# EFM32_power.net
KiCad netlist of a schematic drawn in Altium Designer
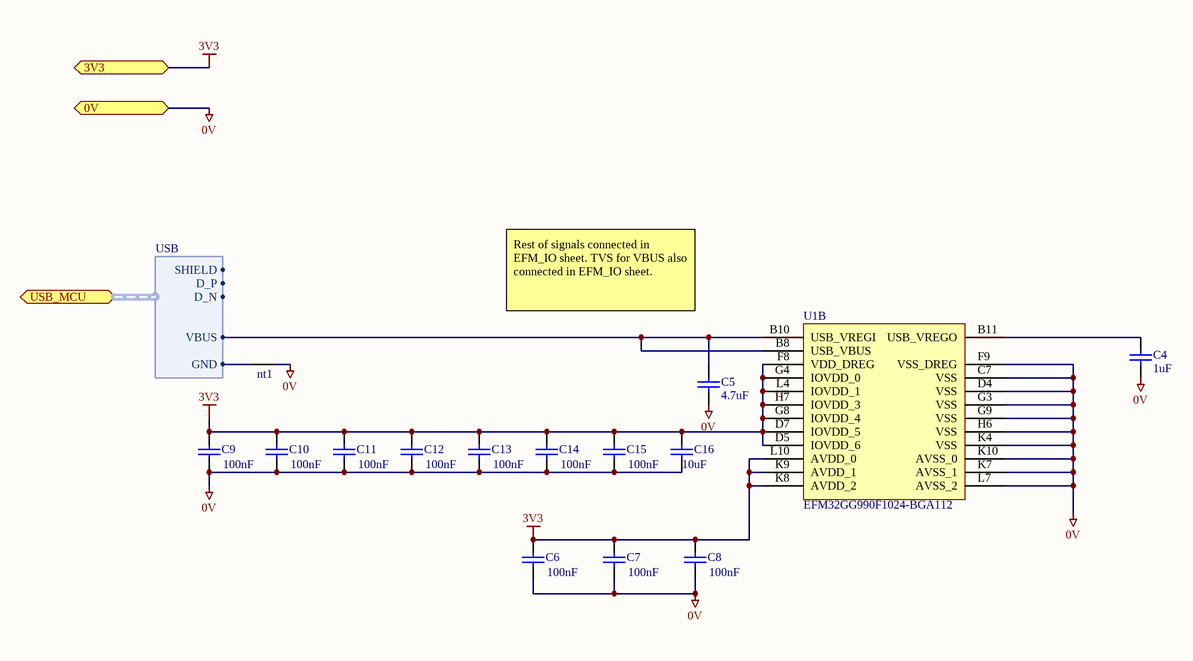
[diagram p0: EFM32_power.SchDoc]

(export (version "E")
  (design (tool "Eeschema 10.0.6"))
  (components
    (comp (ref "C4")
      (value "1uF")
      (footprint "CAPC0603(1608)100_M")
      (description "CAP 1uF 16V ±5% 0603 (1608 Metric) Thickness 1mm SMD")
      (fields (field (name "TOLERANCE") "Â±5%") (field (name "Comment") "CAP 1uF 16V 0603(1608)"))
      (libsource (lib "Altium Content Vault") (part "CMP-1035-02736-1"))
    )
    (comp (ref "C5")
      (value "4.7uF")
      (footprint "CAPC0603(1608)100_M")
      (description "CAP 4.7uF 16V ±10% 0603 (1608 Metric) Thickness 1mm SMD")
      (fields (field (name "TOLERANCE") "Â±10%") (field (name "Comment") "CAP 4.7uF 16V 0603(1608)"))
      (libsource (lib "Altium Content Vault") (part "CMP-1035-02788-1"))
    )
    (comp (ref "C6")
      (value "100nF")
      (footprint "CAPC0603(1608)100_M")
      (description "CAP 100nF 16V ±5% 0603 (1608 Metric) Thickness 1mm SMD")
      (fields (field (name "TOLERANCE") "Â±5%") (field (name "Comment") "CAP 100nF 16V 0603(1608)"))
      (libsource (lib "Altium Content Vault") (part "CMP-1035-02583-1"))
    )
    (comp (ref "C7")
      (value "100nF")
      (footprint "CAPC0603(1608)100_M")
      (description "CAP 100nF 16V ±5% 0603 (1608 Metric) Thickness 1mm SMD")
      (fields (field (name "TOLERANCE") "Â±5%") (field (name "Comment") "CAP 100nF 16V 0603(1608)"))
      (libsource (lib "Altium Content Vault") (part "CMP-1035-02583-1"))
    )
    (comp (ref "C8")
      (value "100nF")
      (footprint "CAPC0603(1608)100_M")
      (description "CAP 100nF 16V ±5% 0603 (1608 Metric) Thickness 1mm SMD")
      (fields (field (name "TOLERANCE") "Â±5%") (field (name "Comment") "CAP 100nF 16V 0603(1608)"))
      (libsource (lib "Altium Content Vault") (part "CMP-1035-02583-1"))
    )
    (comp (ref "C9")
      (value "100nF")
      (footprint "CAPC0603(1608)100_M")
      (description "CAP 100nF 16V ±5% 0603 (1608 Metric) Thickness 1mm SMD")
      (fields (field (name "TOLERANCE") "Â±5%") (field (name "Comment") "CAP 100nF 16V 0603(1608)"))
      (libsource (lib "Altium Content Vault") (part "CMP-1035-02583-1"))
    )
    (comp (ref "C10")
      (value "100nF")
      (footprint "CAPC0603(1608)100_M")
      (description "CAP 100nF 16V ±5% 0603 (1608 Metric) Thickness 1mm SMD")
      (fields (field (name "TOLERANCE") "Â±5%") (field (name "Comment") "CAP 100nF 16V 0603(1608)"))
      (libsource (lib "Altium Content Vault") (part "CMP-1035-02583-1"))
    )
    (comp (ref "C11")
      (value "100nF")
      (footprint "CAPC0603(1608)100_M")
      (description "CAP 100nF 16V ±5% 0603 (1608 Metric) Thickness 1mm SMD")
      (fields (field (name "TOLERANCE") "Â±5%") (field (name "Comment") "CAP 100nF 16V 0603(1608)"))
      (libsource (lib "Altium Content Vault") (part "CMP-1035-02583-1"))
    )
    (comp (ref "C12")
      (value "100nF")
      (footprint "CAPC0603(1608)100_M")
      (description "CAP 100nF 16V ±5% 0603 (1608 Metric) Thickness 1mm SMD")
      (fields (field (name "TOLERANCE") "Â±5%") (field (name "Comment") "CAP 100nF 16V 0603(1608)"))
      (libsource (lib "Altium Content Vault") (part "CMP-1035-02583-1"))
    )
    (comp (ref "C13")
      (value "100nF")
      (footprint "CAPC0603(1608)100_M")
      (description "CAP 100nF 16V ±5% 0603 (1608 Metric) Thickness 1mm SMD")
      (fields (field (name "TOLERANCE") "Â±5%") (field (name "Comment") "CAP 100nF 16V 0603(1608)"))
      (libsource (lib "Altium Content Vault") (part "CMP-1035-02583-1"))
    )
    (comp (ref "C14")
      (value "100nF")
      (footprint "CAPC0603(1608)100_M")
      (description "CAP 100nF 16V ±5% 0603 (1608 Metric) Thickness 1mm SMD")
      (fields (field (name "TOLERANCE") "Â±5%") (field (name "Comment") "CAP 100nF 16V 0603(1608)"))
      (libsource (lib "Altium Content Vault") (part "CMP-1035-02583-1"))
    )
    (comp (ref "C15")
      (value "100nF")
      (footprint "CAPC0603(1608)100_M")
      (description "CAP 100nF 16V ±5% 0603 (1608 Metric) Thickness 1mm SMD")
      (fields (field (name "TOLERANCE") "Â±5%") (field (name "Comment") "CAP 100nF 16V 0603(1608)"))
      (libsource (lib "Altium Content Vault") (part "CMP-1035-02583-1"))
    )
    (comp (ref "C16")
      (value "10uF")
      (footprint "CAPC0603(1608)100_M")
      (description "CAP 10uF 10V ±10% 0603 (1608 Metric) Thickness 1mm SMD")
      (fields (field (name "TOLERANCE") "Â±10%") (field (name "Comment") "CAP 10uF 10V 0603(1608)"))
      (libsource (lib "Altium Content Vault") (part "CMP-1035-02799-1"))
    )
    (comp (ref "nt1")
      (value "net tie")
      (footprint "net tie")
      (description "used to connect nets without transferring net name")
      (libsource (lib "dmpro16lib") (part "net tie"))
    )
    (comp (ref "U1")
      (value "EFM32GG990F1024-BGA112")
      (footprint "ENMR-BGA112")
      (fields (field (name "GENERIC PART NUMBER") "EFM32GG990"))
      (libsource (lib "Altium Content Vault") (part "ENMR-EFM32GG990-BGA112"))
    )
  )
  (nets
    (net (code "2") (name "/GND") (class "Default")
      (node (ref "nt1") (pin "0") (pinfunction "0_0") (pintype "passive"))
    )
    (net (code "3") (name "/VBUS") (class "Default")
      (node (ref "C5") (pin "2") (pinfunction "2_2") (pintype "passive"))
      (node (ref "U1") (pin "B10") (pinfunction "USB_VREGI_B10") (pintype "power_in"))
      (node (ref "U1") (pin "B8") (pinfunction "USB_VBUS_B8") (pintype "power_in"))
    )
    (net (code "5") (name "0V") (class "Default")
      (node (ref "C10") (pin "1") (pinfunction "1_1") (pintype "passive"))
      (node (ref "C11") (pin "1") (pinfunction "1_1") (pintype "passive"))
      (node (ref "C12") (pin "1") (pinfunction "1_1") (pintype "passive"))
      (node (ref "C13") (pin "1") (pinfunction "1_1") (pintype "passive"))
      (node (ref "C14") (pin "1") (pinfunction "1_1") (pintype "passive"))
      (node (ref "C15") (pin "1") (pinfunction "1_1") (pintype "passive"))
      (node (ref "C16") (pin "1") (pinfunction "1_1") (pintype "passive"))
      (node (ref "C4") (pin "1") (pinfunction "1_1") (pintype "passive"))
      (node (ref "C5") (pin "1") (pinfunction "1_1") (pintype "passive"))
      (node (ref "C6") (pin "1") (pinfunction "1_1") (pintype "passive"))
      (node (ref "C7") (pin "1") (pinfunction "1_1") (pintype "passive"))
      (node (ref "C8") (pin "1") (pinfunction "1_1") (pintype "passive"))
      (node (ref "C9") (pin "1") (pinfunction "1_1") (pintype "passive"))
      (node (ref "U1") (pin "C7") (pinfunction "VSS_C7") (pintype "power_in"))
      (node (ref "U1") (pin "D4") (pinfunction "VSS_D4") (pintype "power_in"))
      (node (ref "U1") (pin "F9") (pinfunction "VSS_DREG_F9") (pintype "power_in"))
      (node (ref "U1") (pin "G3") (pinfunction "VSS_G3") (pintype "power_in"))
      (node (ref "U1") (pin "G9") (pinfunction "VSS_G9") (pintype "power_in"))
      (node (ref "U1") (pin "H6") (pinfunction "VSS_H6") (pintype "power_in"))
      (node (ref "U1") (pin "K10") (pinfunction "AVSS_0_K10") (pintype "power_in"))
      (node (ref "U1") (pin "K4") (pinfunction "VSS_K4") (pintype "power_in"))
      (node (ref "U1") (pin "K7") (pinfunction "AVSS_1_K7") (pintype "power_in"))
      (node (ref "U1") (pin "L7") (pinfunction "AVSS_2_L7") (pintype "power_in"))
      (node (ref "nt1") (pin "1") (pinfunction "1_1") (pintype "passive"))
    )
    (net (code "6") (name "3V3") (class "Default")
      (node (ref "C10") (pin "2") (pinfunction "2_2") (pintype "passive"))
      (node (ref "C11") (pin "2") (pinfunction "2_2") (pintype "passive"))
      (node (ref "C12") (pin "2") (pinfunction "2_2") (pintype "passive"))
      (node (ref "C13") (pin "2") (pinfunction "2_2") (pintype "passive"))
      (node (ref "C14") (pin "2") (pinfunction "2_2") (pintype "passive"))
      (node (ref "C15") (pin "2") (pinfunction "2_2") (pintype "passive"))
      (node (ref "C16") (pin "2") (pinfunction "2_2") (pintype "passive"))
      (node (ref "C6") (pin "2") (pinfunction "2_2") (pintype "passive"))
      (node (ref "C7") (pin "2") (pinfunction "2_2") (pintype "passive"))
      (node (ref "C8") (pin "2") (pinfunction "2_2") (pintype "passive"))
      (node (ref "C9") (pin "2") (pinfunction "2_2") (pintype "passive"))
      (node (ref "U1") (pin "D5") (pinfunction "IOVDD_6_D5") (pintype "power_in"))
      (node (ref "U1") (pin "D7") (pinfunction "IOVDD_5_D7") (pintype "power_in"))
      (node (ref "U1") (pin "F8") (pinfunction "VDD_DREG_F8") (pintype "power_in"))
      (node (ref "U1") (pin "G4") (pinfunction "IOVDD_0_G4") (pintype "power_in"))
      (node (ref "U1") (pin "G8") (pinfunction "IOVDD_4_G8") (pintype "power_in"))
      (node (ref "U1") (pin "H7") (pinfunction "IOVDD_3_H7") (pintype "power_in"))
      (node (ref "U1") (pin "K8") (pinfunction "AVDD_2_K8") (pintype "power_in"))
      (node (ref "U1") (pin "K9") (pinfunction "AVDD_1_K9") (pintype "power_in"))
      (node (ref "U1") (pin "L10") (pinfunction "AVDD_0_L10") (pintype "power_in"))
      (node (ref "U1") (pin "L4") (pinfunction "IOVDD_1_L4") (pintype "power_in"))
    )
    (net (code "7") (name "Net-(U1B-USB_VREGO)") (class "Default")
      (node (ref "C4") (pin "2") (pinfunction "2_2") (pintype "passive"))
      (node (ref "U1") (pin "B11") (pinfunction "USB_VREGO_B11") (pintype "passive"))
    )
  )
)
